# design.net
KiCad netlist of a schematic drawn in Altium Designer
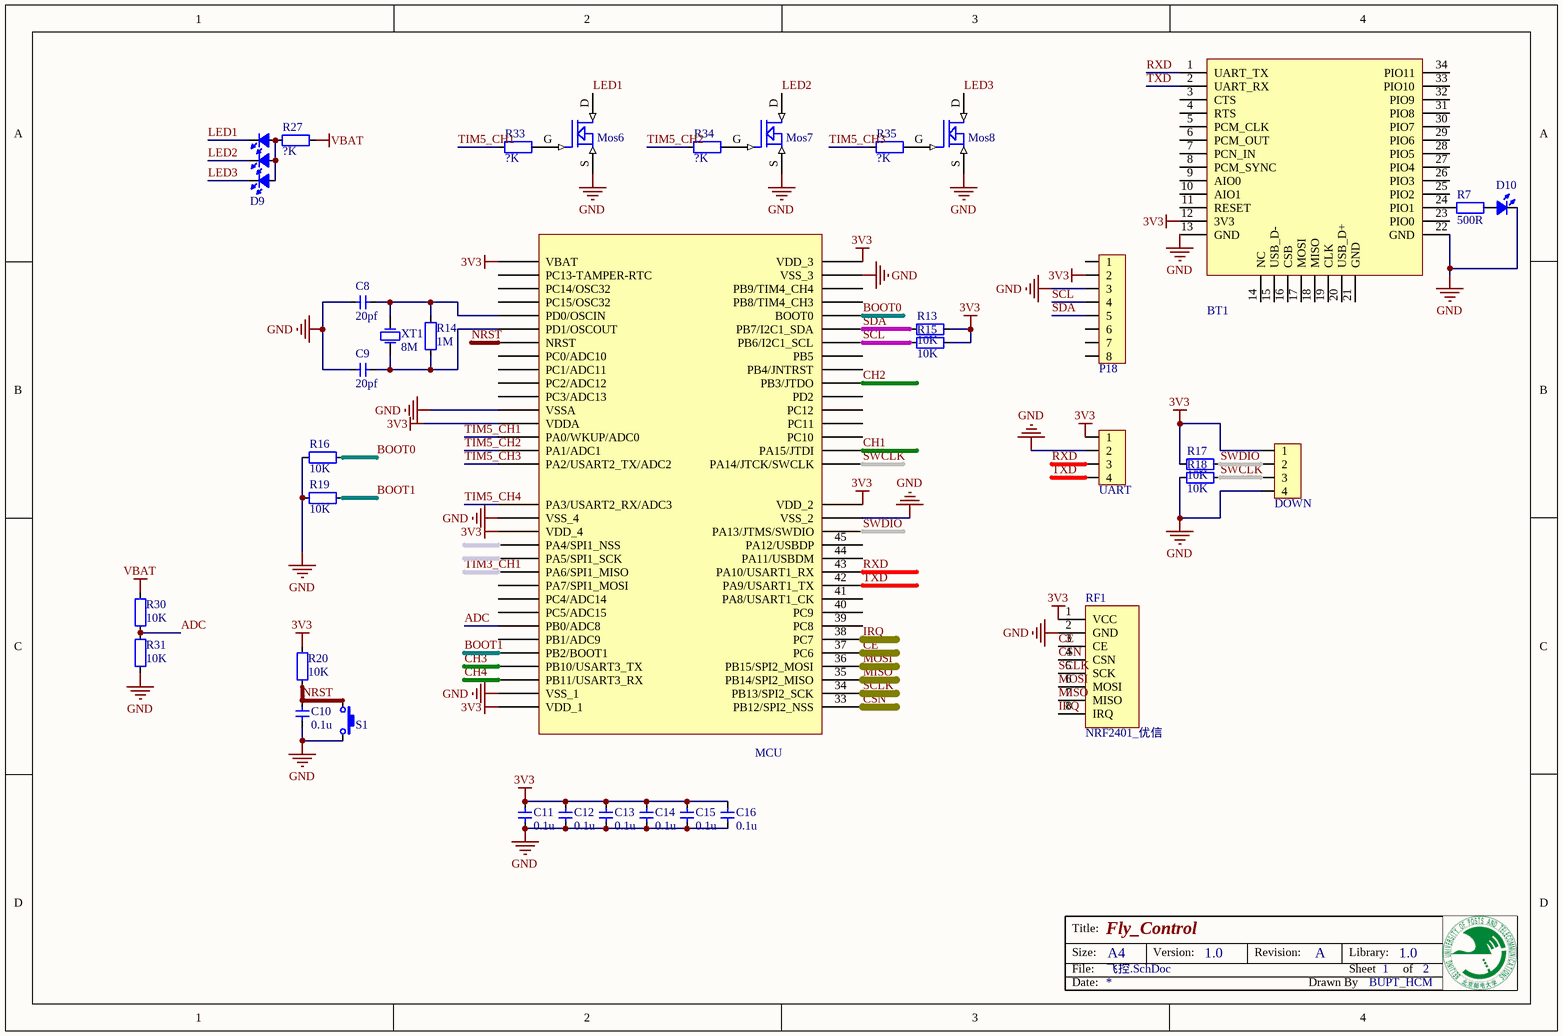
[diagram p0: 飞控.SchDoc]

(export (version "E")
  (design (tool "Eeschema 10.0.6"))
  (components
    (comp (ref "BT1")
      (value "Bluetooth_HC05")
      (footprint "PCB_Module:Bluetooth_HC05")
      (description "Module")
      (libsource (lib "SCH_Module") (part "Bluetooth_HC05"))
    )
    (comp (ref "C8")
      (value "20pf")
      (footprint "PCB_PassiveCap:CAP_0603")
      (description "Capacitor")
      (fields (field (name "Comment") "Cap_0603"))
      (libsource (lib "SCH_Passive") (part "Cap_0603"))
    )
    (comp (ref "C9")
      (value "20pf")
      (footprint "PCB_PassiveCap:CAP_0603")
      (description "Capacitor")
      (fields (field (name "Comment") "Cap_0603"))
      (libsource (lib "SCH_Passive") (part "Cap_0603"))
    )
    (comp (ref "C10")
      (value "0.1u")
      (footprint "PCB_PassiveCap:CAP_0603")
      (description "Capacitor")
      (fields (field (name "Comment") "Cap_0603"))
      (libsource (lib "SCH_Passive") (part "Cap_0603"))
    )
    (comp (ref "C11")
      (value "0.1u")
      (footprint "PCB_PassiveCap:CAP_0603")
      (description "Capacitor")
      (fields (field (name "Comment") "Cap_0603"))
      (libsource (lib "SCH_Passive") (part "Cap_0603"))
    )
    (comp (ref "C12")
      (value "0.1u")
      (footprint "PCB_PassiveCap:CAP_0603")
      (description "Capacitor")
      (fields (field (name "Comment") "Cap_0603"))
      (libsource (lib "SCH_Passive") (part "Cap_0603"))
    )
    (comp (ref "C13")
      (value "0.1u")
      (footprint "PCB_PassiveCap:CAP_0603")
      (description "Capacitor")
      (fields (field (name "Comment") "Cap_0603"))
      (libsource (lib "SCH_Passive") (part "Cap_0603"))
    )
    (comp (ref "C14")
      (value "0.1u")
      (footprint "PCB_PassiveCap:CAP_0603")
      (description "Capacitor")
      (fields (field (name "Comment") "Cap_0603"))
      (libsource (lib "SCH_Passive") (part "Cap_0603"))
    )
    (comp (ref "C15")
      (value "0.1u")
      (footprint "PCB_PassiveCap:CAP_0603")
      (description "Capacitor")
      (fields (field (name "Comment") "Cap_0603"))
      (libsource (lib "SCH_Passive") (part "Cap_0603"))
    )
    (comp (ref "C16")
      (value "0.1u")
      (footprint "PCB_PassiveCap:CAP_0603")
      (description "Capacitor")
      (fields (field (name "Comment") "Cap_0603"))
      (libsource (lib "SCH_Passive") (part "Cap_0603"))
    )
    (comp (ref "D9")
      (value "LED_5050_RGB")
      (footprint "LED_5050_6P")
      (description "LED")
      (libsource (lib "SCH_Active") (part "LED_5050_RGB"))
    )
    (comp (ref "D10")
      (value "LED_0805")
      (footprint "PCB_ActiveLED:LED_0805_BLUE")
      (description "LED")
      (libsource (lib "SCH_Active") (part "LED_0805"))
    )
    (comp (ref "DOWN")
      (value "HDR1x4_2.54")
      (footprint "PCB_ConnectorHDR:HDR1X4_2.54_90")
      (description "Header")
      (libsource (lib "SCH_ConnectorHDR") (part "HDR1x4_2.54"))
    )
    (comp (ref "MCU")
      (value "STM32F103RC")
      (footprint "LQFP_P0.5_64")
      (description "MCU")
      (libsource (lib "SCH_IntegratedCircuit") (part "STM32F103RC"))
    )
    (comp (ref "Mos6")
      (value "MOSFET N")
      (footprint "Nmos_SOT23")
      (description "MOS SOT23")
      (libsource (lib "SCH_Active") (part "MOSFET N"))
    )
    (comp (ref "Mos7")
      (value "MOSFET N")
      (footprint "Nmos_SOT23")
      (description "MOS SOT23")
      (libsource (lib "SCH_Active") (part "MOSFET N"))
    )
    (comp (ref "Mos8")
      (value "MOSFET N")
      (footprint "Nmos_SOT23")
      (description "MOS SOT23")
      (libsource (lib "SCH_Active") (part "MOSFET N"))
    )
    (comp (ref "P18")
      (value "HDR1x8_2.54")
      (footprint "PCB_ConnectorHDR:HDR1X8_2.54_180")
      (description "Header")
      (libsource (lib "SCH_ConnectorHDR") (part "HDR1x8_2.54"))
    )
    (comp (ref "R7")
      (value "500R")
      (footprint "PCB_PassiveRes:RES_0603")
      (description "Resistor")
      (fields (field (name "Comment") "Res_0603"))
      (libsource (lib "") (part "Res_0603_2"))
    )
    (comp (ref "R13")
      (value "10K")
      (footprint "PCB_PassiveRes:RES_0603")
      (description "Resistor")
      (fields (field (name "Comment") "Res_0603"))
      (libsource (lib "") (part "Res_0603_2"))
    )
    (comp (ref "R14")
      (value "1M")
      (footprint "PCB_PassiveRes:RES_0603")
      (description "Resistor")
      (fields (field (name "Comment") "Res_0603"))
      (libsource (lib "SCH_Passive") (part "Res_0603"))
    )
    (comp (ref "R15")
      (value "10K")
      (footprint "PCB_PassiveRes:RES_0603")
      (description "Resistor")
      (fields (field (name "Comment") "Res_0603"))
      (libsource (lib "") (part "Res_0603_2"))
    )
    (comp (ref "R16")
      (value "10K")
      (footprint "PCB_PassiveRes:RES_0603")
      (description "Resistor")
      (fields (field (name "Comment") "Res_0603"))
      (libsource (lib "") (part "Res_0603_3"))
    )
    (comp (ref "R17")
      (value "10K")
      (footprint "PCB_PassiveRes:RES_0603")
      (description "Resistor")
      (fields (field (name "Comment") "Res_0603"))
      (libsource (lib "") (part "Res_0603_3"))
    )
    (comp (ref "R18")
      (value "10K")
      (footprint "PCB_PassiveRes:RES_0603")
      (description "Resistor")
      (fields (field (name "Comment") "Res_0603"))
      (libsource (lib "") (part "Res_0603_3"))
    )
    (comp (ref "R19")
      (value "10K")
      (footprint "PCB_PassiveRes:RES_0603")
      (description "Resistor")
      (fields (field (name "Comment") "Res_0603"))
      (libsource (lib "") (part "Res_0603_3"))
    )
    (comp (ref "R20")
      (value "10K")
      (footprint "PCB_PassiveRes:RES_0603")
      (description "Resistor")
      (fields (field (name "Comment") "Res_0603"))
      (libsource (lib "") (part "Res_0603_1"))
    )
    (comp (ref "R27")
      (value "?K")
      (footprint "PCB_PassiveRes:RES_0603")
      (description "Resistor")
      (fields (field (name "Comment") "Res_0603"))
      (libsource (lib "") (part "Res_0603_3"))
    )
    (comp (ref "R30")
      (value "10K")
      (footprint "PCB_PassiveRes:RES_0603")
      (description "Resistor")
      (fields (field (name "Comment") "Res_0603"))
      (libsource (lib "SCH_Passive") (part "Res_0603"))
    )
    (comp (ref "R31")
      (value "10K")
      (footprint "PCB_PassiveRes:RES_0603")
      (description "Resistor")
      (fields (field (name "Comment") "Res_0603"))
      (libsource (lib "SCH_Passive") (part "Res_0603"))
    )
    (comp (ref "R33")
      (value "?K")
      (footprint "PCB_PassiveRes:RES_0603")
      (description "Resistor")
      (fields (field (name "Comment") "Res_0603"))
      (libsource (lib "") (part "Res_0603_2"))
    )
    (comp (ref "R34")
      (value "?K")
      (footprint "PCB_PassiveRes:RES_0603")
      (description "Resistor")
      (fields (field (name "Comment") "Res_0603"))
      (libsource (lib "") (part "Res_0603_2"))
    )
    (comp (ref "R35")
      (value "?K")
      (footprint "PCB_PassiveRes:RES_0603")
      (description "Resistor")
      (fields (field (name "Comment") "Res_0603"))
      (libsource (lib "") (part "Res_0603_2"))
    )
    (comp (ref "RF1")
      (value "NRF2401_优信")
      (footprint "nrf24l01_youxin")
      (libsource (lib "SCH_Module") (part "NRF2401_优信"))
    )
    (comp (ref "S1")
      (value "ButtonTACT_3x4x2_180")
      (footprint "PCB_Switch:ButtonTACT_3x4x2_180H")
      (description "Button")
      (libsource (lib "SCH_Switch") (part "ButtonTACT_3x4x2_180"))
    )
    (comp (ref "UART")
      (value "HDR1x4_2.54")
      (footprint "PCB_ConnectorHDR:HDR1x4_2.54_180")
      (description "Header")
      (libsource (lib "SCH_ConnectorHDR") (part "HDR1x4_2.54"))
    )
    (comp (ref "XT1")
      (value "8M")
      (footprint "PCB_Oscillator:XT_5032_2")
      (description "Crystal Oscillator")
      (fields (field (name "Comment") "XTAL_5032_2P"))
      (libsource (lib "SCH_Oscillator") (part "XTAL_5032_2P"))
    )
  )
  (nets
    (net (code "1") (name "/ADC") (class "Default")
      (node (ref "MCU") (pin "26") (pinfunction "PB0/ADC8_26") (pintype "passive"))
      (node (ref "R30") (pin "1") (pinfunction "1_1") (pintype "passive"))
      (node (ref "R31") (pin "2") (pinfunction "2_2") (pintype "passive"))
    )
    (net (code "2") (name "/BOOT0") (class "Default")
      (node (ref "MCU") (pin "60") (pinfunction "BOOT0_60") (pintype "passive"))
      (node (ref "R16") (pin "1") (pinfunction "1_1") (pintype "passive"))
    )
    (net (code "3") (name "/BOOT1") (class "Default")
      (node (ref "MCU") (pin "28") (pinfunction "PB2/BOOT1_28") (pintype "passive"))
      (node (ref "R19") (pin "1") (pinfunction "1_1") (pintype "passive"))
    )
    (net (code "4") (name "/CE") (class "Default")
      (node (ref "MCU") (pin "37") (pinfunction "PC6_37") (pintype "passive"))
      (node (ref "RF1") (pin "3") (pinfunction "CE_3") (pintype "passive"))
    )
    (net (code "5") (name "/CH1") (class "Default")
      (node (ref "MCU") (pin "50") (pinfunction "PA15/JTDI_50") (pintype "passive"))
    )
    (net (code "6") (name "/CH2") (class "Default")
      (node (ref "MCU") (pin "55") (pinfunction "PB3/JTDO_55") (pintype "passive"))
    )
    (net (code "7") (name "/CH3") (class "Default")
      (node (ref "MCU") (pin "29") (pinfunction "PB10/USART3_TX_29") (pintype "passive"))
    )
    (net (code "8") (name "/CH4") (class "Default")
      (node (ref "MCU") (pin "30") (pinfunction "PB11/USART3_RX_30") (pintype "passive"))
    )
    (net (code "9") (name "/CSN") (class "Default")
      (node (ref "MCU") (pin "33") (pinfunction "PB12/SPI2_NSS_33") (pintype "passive"))
      (node (ref "RF1") (pin "4") (pinfunction "CSN_4") (pintype "passive"))
    )
    (net (code "10") (name "/IRQ") (class "Default")
      (node (ref "MCU") (pin "38") (pinfunction "PC7_38") (pintype "passive"))
      (node (ref "RF1") (pin "8") (pinfunction "IRQ_8") (pintype "passive"))
    )
    (net (code "11") (name "/LED1") (class "Default")
      (node (ref "D9") (pin "3") (pinfunction "K_3") (pintype "passive"))
      (node (ref "Mos6") (pin "D") (pinfunction "D_D") (pintype "input"))
    )
    (net (code "12") (name "/LED2") (class "Default")
      (node (ref "D9") (pin "2") (pinfunction "K_2") (pintype "passive"))
      (node (ref "Mos7") (pin "D") (pinfunction "D_D") (pintype "input"))
    )
    (net (code "13") (name "/LED3") (class "Default")
      (node (ref "D9") (pin "1") (pinfunction "K_1") (pintype "passive"))
      (node (ref "Mos8") (pin "D") (pinfunction "D_D") (pintype "input"))
    )
    (net (code "14") (name "/MISO") (class "Default")
      (node (ref "MCU") (pin "35") (pinfunction "PB14/SPI2_MISO_35") (pintype "passive"))
      (node (ref "RF1") (pin "7") (pinfunction "MISO_7") (pintype "passive"))
    )
    (net (code "15") (name "/MOSI") (class "Default")
      (node (ref "MCU") (pin "36") (pinfunction "PB15/SPI2_MOSI_36") (pintype "passive"))
      (node (ref "RF1") (pin "6") (pinfunction "MOSI_6") (pintype "passive"))
    )
    (net (code "16") (name "/NRST") (class "Default")
      (node (ref "C10") (pin "2") (pinfunction "2_2") (pintype "passive"))
      (node (ref "MCU") (pin "7") (pinfunction "NRST_7") (pintype "passive"))
      (node (ref "R20") (pin "2") (pinfunction "2_2") (pintype "passive"))
      (node (ref "S1") (pin "1") (pinfunction "1_1") (pintype "passive"))
    )
    (net (code "17") (name "/RXD") (class "Default")
      (node (ref "BT1") (pin "1") (pinfunction "UART_TX_1") (pintype "passive"))
      (node (ref "MCU") (pin "43") (pinfunction "PA10/USART1_RX_43") (pintype "passive"))
      (node (ref "UART") (pin "3") (pinfunction "3_3") (pintype "passive"))
    )
    (net (code "18") (name "/SCL") (class "Default")
      (node (ref "MCU") (pin "58") (pinfunction "PB6/I2C1_SCL_58") (pintype "passive"))
      (node (ref "P18") (pin "4") (pinfunction "4_4") (pintype "passive"))
      (node (ref "R15") (pin "1") (pinfunction "1_1") (pintype "passive"))
    )
    (net (code "19") (name "/SCLK") (class "Default")
      (node (ref "MCU") (pin "34") (pinfunction "PB13/SPI2_SCK_34") (pintype "passive"))
      (node (ref "RF1") (pin "5") (pinfunction "SCK_5") (pintype "passive"))
    )
    (net (code "20") (name "/SDA") (class "Default")
      (node (ref "MCU") (pin "59") (pinfunction "PB7/I2C1_SDA_59") (pintype "passive"))
      (node (ref "P18") (pin "5") (pinfunction "5_5") (pintype "passive"))
      (node (ref "R13") (pin "1") (pinfunction "1_1") (pintype "passive"))
    )
    (net (code "21") (name "/SWCLK") (class "Default")
      (node (ref "DOWN") (pin "3") (pinfunction "3_3") (pintype "passive"))
      (node (ref "MCU") (pin "49") (pinfunction "PA14/JTCK/SWCLK_49") (pintype "passive"))
      (node (ref "R18") (pin "1") (pinfunction "1_1") (pintype "passive"))
    )
    (net (code "22") (name "/SWDIO") (class "Default")
      (node (ref "DOWN") (pin "2") (pinfunction "2_2") (pintype "passive"))
      (node (ref "MCU") (pin "46") (pinfunction "PA13/JTMS/SWDIO_46") (pintype "passive"))
      (node (ref "R17") (pin "1") (pinfunction "1_1") (pintype "passive"))
    )
    (net (code "23") (name "/TIM3_CH1") (class "Default")
      (node (ref "MCU") (pin "22") (pinfunction "PA6/SPI1_MISO_22") (pintype "passive"))
    )
    (net (code "24") (name "/TIM5_CH1") (class "Default")
      (node (ref "MCU") (pin "14") (pinfunction "PA0/WKUP/ADC0_14") (pintype "passive"))
      (node (ref "R33") (pin "1") (pinfunction "1_1") (pintype "passive"))
    )
    (net (code "25") (name "/TIM5_CH2") (class "Default")
      (node (ref "MCU") (pin "15") (pinfunction "PA1/ADC1_15") (pintype "passive"))
      (node (ref "R34") (pin "1") (pinfunction "1_1") (pintype "passive"))
    )
    (net (code "26") (name "/TIM5_CH3") (class "Default")
      (node (ref "MCU") (pin "16") (pinfunction "PA2/USART2_TX/ADC2_16") (pintype "passive"))
      (node (ref "R35") (pin "1") (pinfunction "1_1") (pintype "passive"))
    )
    (net (code "27") (name "/TIM5_CH4") (class "Default")
      (node (ref "MCU") (pin "17") (pinfunction "PA3/USART2_RX/ADC3_17") (pintype "passive"))
    )
    (net (code "28") (name "/TXD") (class "Default")
      (node (ref "BT1") (pin "2") (pinfunction "UART_RX_2") (pintype "passive"))
      (node (ref "MCU") (pin "42") (pinfunction "PA9/USART1_TX_42") (pintype "passive"))
      (node (ref "UART") (pin "4") (pinfunction "4_4") (pintype "passive"))
    )
    (net (code "29") (name "3V3") (class "Default")
      (node (ref "BT1") (pin "12") (pinfunction "3V3_12") (pintype "passive"))
      (node (ref "C11") (pin "2") (pinfunction "2_2") (pintype "passive"))
      (node (ref "C12") (pin "2") (pinfunction "2_2") (pintype "passive"))
      (node (ref "C13") (pin "2") (pinfunction "2_2") (pintype "passive"))
      (node (ref "C14") (pin "2") (pinfunction "2_2") (pintype "passive"))
      (node (ref "C15") (pin "2") (pinfunction "2_2") (pintype "passive"))
      (node (ref "C16") (pin "2") (pinfunction "2_2") (pintype "passive"))
      (node (ref "DOWN") (pin "1") (pinfunction "1_1") (pintype "passive"))
      (node (ref "MCU") (pin "1") (pinfunction "VBAT_1") (pintype "passive"))
      (node (ref "MCU") (pin "13") (pinfunction "VDDA_13") (pintype "passive"))
      (node (ref "MCU") (pin "19") (pinfunction "VDD_4_19") (pintype "passive"))
      (node (ref "MCU") (pin "32") (pinfunction "VDD_1_32") (pintype "passive"))
      (node (ref "MCU") (pin "48") (pinfunction "VDD_2_48") (pintype "passive"))
      (node (ref "MCU") (pin "64") (pinfunction "VDD_3_64") (pintype "passive"))
      (node (ref "P18") (pin "2") (pinfunction "2_2") (pintype "passive"))
      (node (ref "R13") (pin "2") (pinfunction "2_2") (pintype "passive"))
      (node (ref "R15") (pin "2") (pinfunction "2_2") (pintype "passive"))
      (node (ref "R17") (pin "2") (pinfunction "2_2") (pintype "passive"))
      (node (ref "R20") (pin "1") (pinfunction "1_1") (pintype "passive"))
      (node (ref "RF1") (pin "1") (pinfunction "VCC_1") (pintype "passive"))
      (node (ref "UART") (pin "1") (pinfunction "1_1") (pintype "passive"))
    )
    (net (code "30") (name "GND") (class "Default")
      (node (ref "BT1") (pin "13") (pinfunction "GND_13") (pintype "passive"))
      (node (ref "BT1") (pin "22") (pinfunction "GND_22") (pintype "passive"))
      (node (ref "C10") (pin "1") (pinfunction "1_1") (pintype "passive"))
      (node (ref "C11") (pin "1") (pinfunction "1_1") (pintype "passive"))
      (node (ref "C12") (pin "1") (pinfunction "1_1") (pintype "passive"))
      (node (ref "C13") (pin "1") (pinfunction "1_1") (pintype "passive"))
      (node (ref "C14") (pin "1") (pinfunction "1_1") (pintype "passive"))
      (node (ref "C15") (pin "1") (pinfunction "1_1") (pintype "passive"))
      (node (ref "C16") (pin "1") (pinfunction "1_1") (pintype "passive"))
      (node (ref "C8") (pin "1") (pinfunction "1_1") (pintype "passive"))
      (node (ref "C9") (pin "1") (pinfunction "1_1") (pintype "passive"))
      (node (ref "D10") (pin "2") (pinfunction "K_2") (pintype "passive"))
      (node (ref "DOWN") (pin "4") (pinfunction "4_4") (pintype "passive"))
      (node (ref "MCU") (pin "12") (pinfunction "VSSA_12") (pintype "passive"))
      (node (ref "MCU") (pin "18") (pinfunction "VSS_4_18") (pintype "passive"))
      (node (ref "MCU") (pin "31") (pinfunction "VSS_1_31") (pintype "passive"))
      (node (ref "MCU") (pin "47") (pinfunction "VSS_2_47") (pintype "passive"))
      (node (ref "MCU") (pin "63") (pinfunction "VSS_3_63") (pintype "passive"))
      (node (ref "Mos6") (pin "S") (pinfunction "S_S") (pintype "input"))
      (node (ref "Mos7") (pin "S") (pinfunction "S_S") (pintype "input"))
      (node (ref "Mos8") (pin "S") (pinfunction "S_S") (pintype "input"))
      (node (ref "P18") (pin "3") (pinfunction "3_3") (pintype "passive"))
      (node (ref "R16") (pin "2") (pinfunction "2_2") (pintype "passive"))
      (node (ref "R18") (pin "2") (pinfunction "2_2") (pintype "passive"))
      (node (ref "R19") (pin "2") (pinfunction "2_2") (pintype "passive"))
      (node (ref "R31") (pin "1") (pinfunction "1_1") (pintype "passive"))
      (node (ref "RF1") (pin "2") (pinfunction "GND_2") (pintype "passive"))
      (node (ref "S1") (pin "2") (pinfunction "2_2") (pintype "passive"))
      (node (ref "UART") (pin "2") (pinfunction "2_2") (pintype "passive"))
    )
    (net (code "31") (name "Net-(BT1-PIO1)") (class "Default")
      (node (ref "BT1") (pin "24") (pinfunction "PIO1_24") (pintype "passive"))
      (node (ref "R7") (pin "1") (pinfunction "1_1") (pintype "passive"))
    )
    (net (code "32") (name "Net-(D9-A-Pad4)") (class "Default")
      (node (ref "D9") (pin "4") (pinfunction "A_4") (pintype "passive"))
      (node (ref "D9") (pin "5") (pinfunction "A_5") (pintype "passive"))
      (node (ref "D9") (pin "6") (pinfunction "A_6") (pintype "passive"))
      (node (ref "R27") (pin "2") (pinfunction "2_2") (pintype "passive"))
    )
    (net (code "33") (name "Net-(D10-A)") (class "Default")
      (node (ref "D10") (pin "1") (pinfunction "A_1") (pintype "passive"))
      (node (ref "R7") (pin "2") (pinfunction "2_2") (pintype "passive"))
    )
    (net (code "34") (name "Net-(MCU-PD0{slash}OSCIN)") (class "Default")
      (node (ref "C8") (pin "2") (pinfunction "2_2") (pintype "passive"))
      (node (ref "MCU") (pin "5") (pinfunction "PD0/OSCIN_5") (pintype "passive"))
      (node (ref "R14") (pin "2") (pinfunction "2_2") (pintype "passive"))
      (node (ref "XT1") (pin "2") (pinfunction "OSC2_2") (pintype "passive"))
    )
    (net (code "35") (name "Net-(MCU-PD1{slash}OSCOUT)") (class "Default")
      (node (ref "C9") (pin "2") (pinfunction "2_2") (pintype "passive"))
      (node (ref "MCU") (pin "6") (pinfunction "PD1/OSCOUT_6") (pintype "passive"))
      (node (ref "R14") (pin "1") (pinfunction "1_1") (pintype "passive"))
      (node (ref "XT1") (pin "1") (pinfunction "OSC1_1") (pintype "passive"))
    )
    (net (code "36") (name "Net-(Mos6-PadG)") (class "Default")
      (node (ref "Mos6") (pin "G") (pinfunction "G_G") (pintype "input"))
      (node (ref "R33") (pin "2") (pinfunction "2_2") (pintype "passive"))
    )
    (net (code "37") (name "Net-(Mos7-PadG)") (class "Default")
      (node (ref "Mos7") (pin "G") (pinfunction "G_G") (pintype "input"))
      (node (ref "R34") (pin "2") (pinfunction "2_2") (pintype "passive"))
    )
    (net (code "38") (name "Net-(Mos8-PadG)") (class "Default")
      (node (ref "Mos8") (pin "G") (pinfunction "G_G") (pintype "input"))
      (node (ref "R35") (pin "2") (pinfunction "2_2") (pintype "passive"))
    )
    (net (code "39") (name "VBAT") (class "Default")
      (node (ref "R27") (pin "1") (pinfunction "1_1") (pintype "passive"))
      (node (ref "R30") (pin "2") (pinfunction "2_2") (pintype "passive"))
    )
    (net (code "40") (name "unconnected-(BT1-AIO0-Pad9)") (class "Default")
      (node (ref "BT1") (pin "9") (pinfunction "AIO0_9") (pintype "passive"))
    )
    (net (code "41") (name "unconnected-(BT1-AIO1-Pad10)") (class "Default")
      (node (ref "BT1") (pin "10") (pinfunction "AIO1_10") (pintype "passive"))
    )
    (net (code "42") (name "unconnected-(BT1-CLK-Pad19)") (class "Default")
      (node (ref "BT1") (pin "19") (pinfunction "CLK_19") (pintype "passive"))
    )
    (net (code "43") (name "unconnected-(BT1-CSB-Pad16)") (class "Default")
      (node (ref "BT1") (pin "16") (pinfunction "CSB_16") (pintype "passive"))
    )
    (net (code "44") (name "unconnected-(BT1-CTS-Pad3)") (class "Default")
      (node (ref "BT1") (pin "3") (pinfunction "CTS_3") (pintype "passive"))
    )
    (net (code "45") (name "unconnected-(BT1-GND-Pad21)") (class "Default")
      (node (ref "BT1") (pin "21") (pinfunction "GND_21") (pintype "passive"))
    )
    (net (code "46") (name "unconnected-(BT1-MISO-Pad18)") (class "Default")
      (node (ref "BT1") (pin "18") (pinfunction "MISO_18") (pintype "passive"))
    )
    (net (code "47") (name "unconnected-(BT1-MOSI-Pad17)") (class "Default")
      (node (ref "BT1") (pin "17") (pinfunction "MOSI_17") (pintype "passive"))
    )
    (net (code "48") (name "unconnected-(BT1-NC-Pad14)") (class "Default")
      (node (ref "BT1") (pin "14") (pinfunction "NC_14") (pintype "passive"))
    )
    (net (code "49") (name "unconnected-(BT1-PCM_CLK-Pad5)") (class "Default")
      (node (ref "BT1") (pin "5") (pinfunction "PCM_CLK_5") (pintype "passive"))
    )
    (net (code "50") (name "unconnected-(BT1-PCM_OUT-Pad6)") (class "Default")
      (node (ref "BT1") (pin "6") (pinfunction "PCM_OUT_6") (pintype "passive"))
    )
    (net (code "51") (name "unconnected-(BT1-PCM_SYNC-Pad8)") (class "Default")
      (node (ref "BT1") (pin "8") (pinfunction "PCM_SYNC_8") (pintype "passive"))
    )
    (net (code "52") (name "unconnected-(BT1-PCN_IN-Pad7)") (class "Default")
      (node (ref "BT1") (pin "7") (pinfunction "PCN_IN_7") (pintype "passive"))
    )
    (net (code "53") (name "unconnected-(BT1-PIO0-Pad23)") (class "Default")
      (node (ref "BT1") (pin "23") (pinfunction "PIO0_23") (pintype "passive"))
    )
    (net (code "54") (name "unconnected-(BT1-PIO2-Pad25)") (class "Default")
      (node (ref "BT1") (pin "25") (pinfunction "PIO2_25") (pintype "passive"))
    )
    (net (code "55") (name "unconnected-(BT1-PIO3-Pad26)") (class "Default")
      (node (ref "BT1") (pin "26") (pinfunction "PIO3_26") (pintype "passive"))
    )
    (net (code "56") (name "unconnected-(BT1-PIO4-Pad27)") (class "Default")
      (node (ref "BT1") (pin "27") (pinfunction "PIO4_27") (pintype "passive"))
    )
    (net (code "57") (name "unconnected-(BT1-PIO5-Pad28)") (class "Default")
      (node (ref "BT1") (pin "28") (pinfunction "PIO5_28") (pintype "passive"))
    )
    (net (code "58") (name "unconnected-(BT1-PIO6-Pad29)") (class "Default")
      (node (ref "BT1") (pin "29") (pinfunction "PIO6_29") (pintype "passive"))
    )
    (net (code "59") (name "unconnected-(BT1-PIO7-Pad30)") (class "Default")
      (node (ref "BT1") (pin "30") (pinfunction "PIO7_30") (pintype "passive"))
    )
    (net (code "60") (name "unconnected-(BT1-PIO8-Pad31)") (class "Default")
      (node (ref "BT1") (pin "31") (pinfunction "PIO8_31") (pintype "passive"))
    )
    (net (code "61") (name "unconnected-(BT1-PIO9-Pad32)") (class "Default")
      (node (ref "BT1") (pin "32") (pinfunction "PIO9_32") (pintype "passive"))
    )
    (net (code "62") (name "unconnected-(BT1-PIO10-Pad33)") (class "Default")
      (node (ref "BT1") (pin "33") (pinfunction "PIO10_33") (pintype "passive"))
    )
    (net (code "63") (name "unconnected-(BT1-PIO11-Pad34)") (class "Default")
      (node (ref "BT1") (pin "34") (pinfunction "PIO11_34") (pintype "passive"))
    )
    (net (code "64") (name "unconnected-(BT1-RESET-Pad11)") (class "Default")
      (node (ref "BT1") (pin "11") (pinfunction "RESET_11") (pintype "passive"))
    )
    (net (code "65") (name "unconnected-(BT1-RTS-Pad4)") (class "Default")
      (node (ref "BT1") (pin "4") (pinfunction "RTS_4") (pintype "passive"))
    )
    (net (code "66") (name "unconnected-(BT1-USB_D+-Pad20)") (class "Default")
      (node (ref "BT1") (pin "20") (pinfunction "USB_D+_20") (pintype "passive"))
    )
    (net (code "67") (name "unconnected-(BT1-USB_D--Pad15)") (class "Default")
      (node (ref "BT1") (pin "15") (pinfunction "USB_D-_15") (pintype "passive"))
    )
    (net (code "68") (name "unconnected-(MCU-PA4{slash}SPI1_NSS-Pad20)") (class "Default")
      (node (ref "MCU") (pin "20") (pinfunction "PA4/SPI1_NSS_20") (pintype "passive"))
    )
    (net (code "69") (name "unconnected-(MCU-PA5{slash}SPI1_SCK-Pad21)") (class "Default")
      (node (ref "MCU") (pin "21") (pinfunction "PA5/SPI1_SCK_21") (pintype "passive"))
    )
    (net (code "70") (name "unconnected-(MCU-PA7{slash}SPI1_MOSI-Pad23)") (class "Default")
      (node (ref "MCU") (pin "23") (pinfunction "PA7/SPI1_MOSI_23") (pintype "passive"))
    )
    (net (code "71") (name "unconnected-(MCU-PA8{slash}USART1_CK-Pad41)") (class "Default")
      (node (ref "MCU") (pin "41") (pinfunction "PA8/USART1_CK_41") (pintype "passive"))
    )
    (net (code "72") (name "unconnected-(MCU-PA11{slash}USBDM-Pad44)") (class "Default")
      (node (ref "MCU") (pin "44") (pinfunction "PA11/USBDM_44") (pintype "passive"))
    )
    (net (code "73") (name "unconnected-(MCU-PA12{slash}USBDP-Pad45)") (class "Default")
      (node (ref "MCU") (pin "45") (pinfunction "PA12/USBDP_45") (pintype "passive"))
    )
    (net (code "74") (name "unconnected-(MCU-PB1{slash}ADC9-Pad27)") (class "Default")
      (node (ref "MCU") (pin "27") (pinfunction "PB1/ADC9_27") (pintype "passive"))
    )
    (net (code "75") (name "unconnected-(MCU-PB4{slash}JNTRST-Pad56)") (class "Default")
      (node (ref "MCU") (pin "56") (pinfunction "PB4/JNTRST_56") (pintype "passive"))
    )
    (net (code "76") (name "unconnected-(MCU-PB5-Pad57)") (class "Default")
      (node (ref "MCU") (pin "57") (pinfunction "PB5_57") (pintype "passive"))
    )
    (net (code "77") (name "unconnected-(MCU-PB8{slash}TIM4_CH3-Pad61)") (class "Default")
      (node (ref "MCU") (pin "61") (pinfunction "PB8/TIM4_CH3_61") (pintype "passive"))
    )
    (net (code "78") (name "unconnected-(MCU-PB9{slash}TIM4_CH4-Pad62)") (class "Default")
      (node (ref "MCU") (pin "62") (pinfunction "PB9/TIM4_CH4_62") (pintype "passive"))
    )
    (net (code "79") (name "unconnected-(MCU-PC0{slash}ADC10-Pad8)") (class "Default")
      (node (ref "MCU") (pin "8") (pinfunction "PC0/ADC10_8") (pintype "passive"))
    )
    (net (code "80") (name "unconnected-(MCU-PC1{slash}ADC11-Pad9)") (class "Default")
      (node (ref "MCU") (pin "9") (pinfunction "PC1/ADC11_9") (pintype "passive"))
    )
    (net (code "81") (name "unconnected-(MCU-PC2{slash}ADC12-Pad10)") (class "Default")
      (node (ref "MCU") (pin "10") (pinfunction "PC2/ADC12_10") (pintype "passive"))
    )
    (net (code "82") (name "unconnected-(MCU-PC3{slash}ADC13-Pad11)") (class "Default")
      (node (ref "MCU") (pin "11") (pinfunction "PC3/ADC13_11") (pintype "passive"))
    )
    (net (code "83") (name "unconnected-(MCU-PC4{slash}ADC14-Pad24)") (class "Default")
      (node (ref "MCU") (pin "24") (pinfunction "PC4/ADC14_24") (pintype "passive"))
    )
    (net (code "84") (name "unconnected-(MCU-PC5{slash}ADC15-Pad25)") (class "Default")
      (node (ref "MCU") (pin "25") (pinfunction "PC5/ADC15_25") (pintype "passive"))
    )
    (net (code "85") (name "unconnected-(MCU-PC8-Pad39)") (class "Default")
      (node (ref "MCU") (pin "39") (pinfunction "PC8_39") (pintype "passive"))
    )
    (net (code "86") (name "unconnected-(MCU-PC9-Pad40)") (class "Default")
      (node (ref "MCU") (pin "40") (pinfunction "PC9_40") (pintype "passive"))
    )
    (net (code "87") (name "unconnected-(MCU-PC10-Pad51)") (class "Default")
      (node (ref "MCU") (pin "51") (pinfunction "PC10_51") (pintype "passive"))
    )
    (net (code "88") (name "unconnected-(MCU-PC11-Pad52)") (class "Default")
      (node (ref "MCU") (pin "52") (pinfunction "PC11_52") (pintype "passive"))
    )
    (net (code "89") (name "unconnected-(MCU-PC12-Pad53)") (class "Default")
      (node (ref "MCU") (pin "53") (pinfunction "PC12_53") (pintype "passive"))
    )
    (net (code "90") (name "unconnected-(MCU-PC13-TAMPER-RTC-Pad2)") (class "Default")
      (node (ref "MCU") (pin "2") (pinfunction "PC13-TAMPER-RTC_2") (pintype "passive"))
    )
    (net (code "91") (name "unconnected-(MCU-PC14{slash}OSC32-Pad3)") (class "Default")
      (node (ref "MCU") (pin "3") (pinfunction "PC14/OSC32_3") (pintype "passive"))
    )
    (net (code "92") (name "unconnected-(MCU-PC15{slash}OSC32-Pad4)") (class "Default")
      (node (ref "MCU") (pin "4") (pinfunction "PC15/OSC32_4") (pintype "passive"))
    )
    (net (code "93") (name "unconnected-(MCU-PD2-Pad54)") (class "Default")
      (node (ref "MCU") (pin "54") (pinfunction "PD2_54") (pintype "passive"))
    )
    (net (code "94") (name "unconnected-(P18-Pad1)") (class "Default")
      (node (ref "P18") (pin "1") (pinfunction "1_1") (pintype "passive"))
    )
    (net (code "95") (name "unconnected-(P18-Pad6)") (class "Default")
      (node (ref "P18") (pin "6") (pinfunction "6_6") (pintype "passive"))
    )
    (net (code "96") (name "unconnected-(P18-Pad7)") (class "Default")
      (node (ref "P18") (pin "7") (pinfunction "7_7") (pintype "passive"))
    )
    (net (code "97") (name "unconnected-(P18-Pad8)") (class "Default")
      (node (ref "P18") (pin "8") (pinfunction "8_8") (pintype "passive"))
    )
  )
)
